# USB.net
KiCad netlist of a schematic drawn in Altium Designer
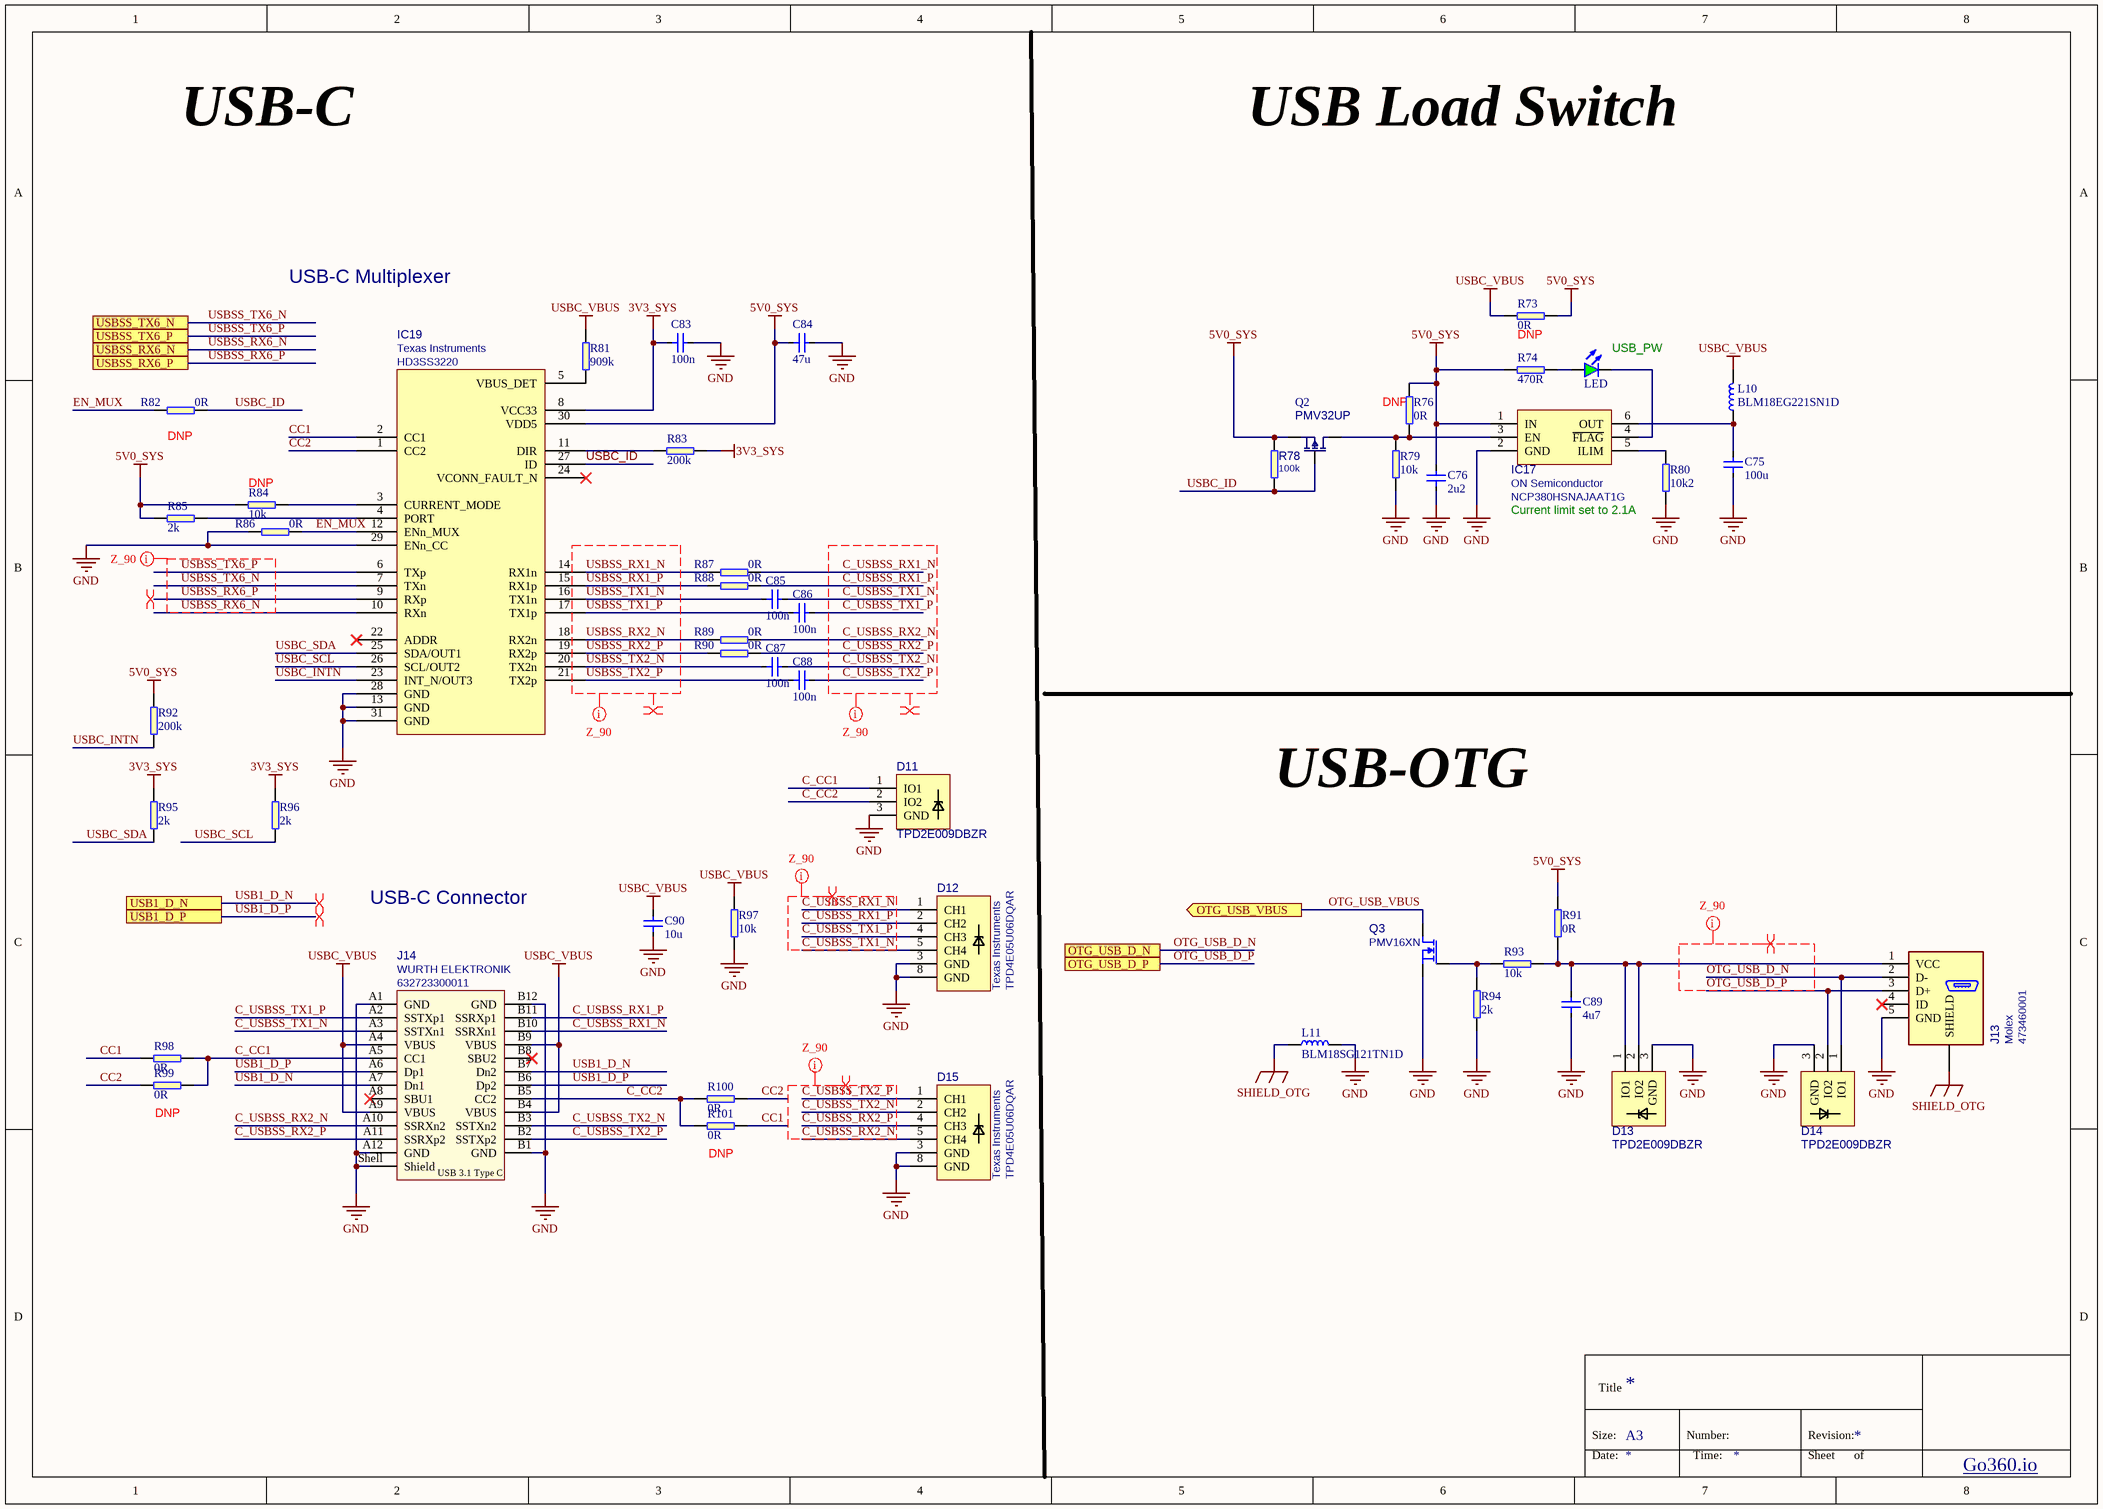
[diagram p0: USB.SchDoc]

(export (version "E")
  (design (tool "Eeschema 10.0.6"))
  (components
    (comp (ref "C75")
      (value "100u")
      (footprint "1206")
      (description "MLCC SMT Capacitor 100uF 1206")
      (fields (field (name "PARTNUMBER") "C_100u_1206") (field (name "MANUFACTURER") "Taiyo Yuden"))
      (libsource (lib "jetson-nano-baseboard") (part "C_100u_1206"))
    )
    (comp (ref "C76")
      (value "2u2")
      (footprint "C0402")
      (description "MLCC SMT Capacitor 2.2uF 0402")
      (fields (field (name "PARTNUMBER") "C_2u2_0402") (field (name "MANUFACTURER") "TDK"))
      (libsource (lib "jetson-nano-baseboard") (part "C_2u2_0402"))
    )
    (comp (ref "C83")
      (value "100n")
      (footprint "C0402")
      (description "MLCC SMT Capacitor 100n 0402")
      (fields (field (name "PARTNUMBER") "C_100n_0402") (field (name "MANUFACTURER") "TDK"))
      (libsource (lib "jetson-nano-baseboard") (part "C_100n_0402"))
    )
    (comp (ref "C84")
      (value "47u")
      (footprint "0805")
      (description "MLCC SMT Capacitor 47uF 0805")
      (fields (field (name "PARTNUMBER") "C_47u_0805") (field (name "MANUFACTURER") "KEMET"))
      (libsource (lib "jetson-nano-baseboard") (part "C_47u_0805"))
    )
    (comp (ref "C85")
      (value "100n")
      (footprint "C0402")
      (description "MLCC SMT Capacitor 100n 0402")
      (fields (field (name "PARTNUMBER") "C_100n_0402") (field (name "MANUFACTURER") "TDK"))
      (libsource (lib "jetson-nano-baseboard") (part "C_100n_0402"))
    )
    (comp (ref "C86")
      (value "100n")
      (footprint "C0402")
      (description "MLCC SMT Capacitor 100n 0402")
      (fields (field (name "PARTNUMBER") "C_100n_0402") (field (name "MANUFACTURER") "TDK"))
      (libsource (lib "jetson-nano-baseboard") (part "C_100n_0402"))
    )
    (comp (ref "C87")
      (value "100n")
      (footprint "C0402")
      (description "MLCC SMT Capacitor 100n 0402")
      (fields (field (name "PARTNUMBER") "C_100n_0402") (field (name "MANUFACTURER") "TDK"))
      (libsource (lib "jetson-nano-baseboard") (part "C_100n_0402"))
    )
    (comp (ref "C88")
      (value "100n")
      (footprint "C0402")
      (description "MLCC SMT Capacitor 100n 0402")
      (fields (field (name "PARTNUMBER") "C_100n_0402") (field (name "MANUFACTURER") "TDK"))
      (libsource (lib "jetson-nano-baseboard") (part "C_100n_0402"))
    )
    (comp (ref "C89")
      (value "4u7")
      (footprint "C0402")
      (description "MLCC SMT Capacitor 4.7uF 0402")
      (fields (field (name "PARTNUMBER") "C_4u7_0402") (field (name "MANUFACTURER") "MURATA"))
      (libsource (lib "jetson-nano-baseboard") (part "C_4u7_0402"))
    )
    (comp (ref "C90")
      (value "10u")
      (footprint "C0603")
      (description "MLCC SMT Capacitor 10uF 0603")
      (fields (field (name "PARTNUMBER") "C_10u_0603") (field (name "MANUFACTURER") "Walsin"))
      (libsource (lib "jetson-nano-baseboard") (part "C_10u_0603"))
    )
    (comp (ref "D11")
      (value "TPD2E009DBZR")
      (footprint "SOT-23")
      (description "DIODE, SCHOTTKY, 30V, 200MA, SOT-23")
      (fields (field (name "MANUFACTURER") "NXP"))
      (libsource (lib "") (part "TPD2E009DBZR_1"))
    )
    (comp (ref "D12")
      (value "TPD4E05U06")
      (footprint "TPD4E05U06_PASS")
      (description "ESD Suppressors 4-CH")
      (fields
        (field (name "PARTNUMBER") "TPD4E05U06_PASS")
        (field (name "MANUFACTURER") "Texas Instruments")
        (field (name "PARTSYMBOL") "TPD4E05U06DQAR")
      )
      (libsource (lib "jetson-nano-baseboard") (part "TPD4E05U06"))
    )
    (comp (ref "D13")
      (value "TPD2E009DBZR")
      (footprint "SOT-23s")
      (description "DIODE, SCHOTTKY, 30V, 200MA, SOT-23")
      (fields (field (name "MANUFACTURER") "NXP"))
      (libsource (lib "") (part "TPD2E009DBZR_2"))
    )
    (comp (ref "D14")
      (value "TPD2E009DBZR")
      (footprint "SOT-23s")
      (description "DIODE, SCHOTTKY, 30V, 200MA, SOT-23")
      (fields (field (name "MANUFACTURER") "NXP"))
      (libsource (lib "jetson-nano-baseboard") (part "TPD2E009DBZR"))
    )
    (comp (ref "D15")
      (value "TPD4E05U06")
      (footprint "TPD4E05U06_PASS")
      (description "ESD Suppressors 4-CH")
      (fields
        (field (name "PARTNUMBER") "TPD4E05U06_PASS")
        (field (name "MANUFACTURER") "Texas Instruments")
        (field (name "PARTSYMBOL") "TPD4E05U06DQAR")
      )
      (libsource (lib "jetson-nano-baseboard") (part "TPD4E05U06"))
    )
    (comp (ref "IC17")
      (value "NCP380HSNAJAAT1G")
      (footprint "TSOP-6")
      (description "POWER LOAD SWITCH, HIGH SIDE")
      (fields (field (name "MANUFACTURER") "ON Semiconductor"))
      (libsource (lib "jetson-nano-baseboard") (part "NCP380HSNAJAAT1G"))
    )
    (comp (ref "IC19")
      (value "HD3SS3220")
      (footprint "RNH0030A")
      (description "IC DRP PORT CTLR USB-C 30WQFN")
      (fields (field (name "MANUFACTURER") "Texas Instruments"))
      (libsource (lib "jetson-nano-baseboard") (part "HD3SS3220"))
    )
    (comp (ref "J13")
      (value "Molex 47346-0001")
      (footprint "CON-Molex-047346-0001")
      (description "USB - micro B Receptacle Connector 5 Position Surface Mount, Right Angle, Horizontal")
      (fields
        (field (name "PARTNUMBER") "CON-Molex-47346-0001")
        (field (name "MANUFACTURER") "Molex")
        (field (name "PARTSYMBOL") "473460001")
      )
      (libsource (lib "jetson-nano-baseboard") (part "Micro USB B"))
    )
    (comp (ref "J14")
      (value "632723300011")
      (footprint "WE_632723300011")
      (description "USB 3.1 Type C Receptacle Horizontal THR WR-COM")
      (fields (field (name "PARTNUMBER") "WE_632723300011") (field (name "MANUFACTURER") "WURTH ELEKTRONIK"))
      (libsource (lib "jetson-nano-baseboard") (part "WE_632723300011"))
    )
    (comp (ref "L10")
      (value "BLM18EG221SN1D")
      (footprint "BEADC1608X65N")
      (description "MURATA  BLM18EG221SN1D  FERRITE BEAD, 0.05OHM, 2A, 0603")
      (fields (field (name "MANUFACTURER") "MURATA"))
      (libsource (lib "jetson-nano-baseboard") (part "BLM18EG221SN1D"))
    )
    (comp (ref "L11")
      (value "BLM18SG121TN1D")
      (footprint "BEADC1608X65N")
      (description "FERRITE BEAD, 0.025OHM, 3A, 0603")
      (fields (field (name "MANUFACTURER") "MURATA"))
      (libsource (lib "jetson-nano-baseboard") (part "BLM18SG121TN1D"))
    )
    (comp (ref "LED")
      (value "SML-310MTT86")
      (footprint "LED0603")
      (description "LED Green 0603 case")
      (fields (field (name "MANUFACTURER") "ROHM Semicon") (field (name "PARTNUMBER") "LED_G"))
      (libsource (lib "jetson-nano-baseboard") (part "LED"))
    )
    (comp (ref "Q2")
      (value "PMV32UP")
      (footprint "SOT-23s")
      (description "P CH, 20V, 4A")
      (fields (field (name "MANUFACTURER") "NXP"))
      (libsource (lib "jetson-nano-baseboard") (part "PMOS"))
    )
    (comp (ref "Q3")
      (value "PMV16XN")
      (footprint "SOT-23s")
      (description "MOSFET, N CH")
      (fields (field (name "MANUFACTURER") "NXP"))
      (libsource (lib "jetson-nano-baseboard") (part "NMOS_PMV16XN"))
    )
    (comp (ref "R73")
      (value "0R")
      (footprint "R0402")
      (description "RES, 0R, 0402")
      (fields (field (name "PARTNUMBER") "R_0R_0402") (field (name "MANUFACTURER") "Panasonic"))
      (libsource (lib "") (part "R_0R_0402_1"))
    )
    (comp (ref "R74")
      (value "470R")
      (footprint "R0402")
      (description "RES, 470R, 0402")
      (fields (field (name "PARTNUMBER") "R_470R_0402") (field (name "MANUFACTURER") "VISHAY"))
      (libsource (lib "jetson-nano-baseboard") (part "R_470R_0402"))
    )
    (comp (ref "R76")
      (value "0R")
      (footprint "R0402")
      (description "RES, 0R, 0402")
      (fields (field (name "PARTNUMBER") "R_0R_0402") (field (name "MANUFACTURER") "Panasonic"))
      (libsource (lib "") (part "R_0R_0402_2"))
    )
    (comp (ref "R78")
      (value "100k")
      (footprint "R0402")
      (description "SMT Resistor 100k 0402")
      (fields (field (name "PARTNUMBER") "R_100k_0402") (field (name "TOLERANCE") "1%"))
      (libsource (lib "jetson-nano-baseboard") (part "R_100k_0402"))
    )
    (comp (ref "R79")
      (value "10k")
      (footprint "R0402")
      (description "RES, 10k, 0402")
      (fields (field (name "PARTNUMBER") "R_10k_0402") (field (name "MANUFACTURER") "MULTICOMP"))
      (libsource (lib "jetson-nano-baseboard") (part "R_10k_0402"))
    )
    (comp (ref "R80")
      (value "10k2")
      (footprint "R0402")
      (description "RES, 10k2, 0402, 0.1%")
      (fields (field (name "PARTNUMBER") "R_10k2_0402_0.1%") (field (name "TOLERANCE") "0.1%"))
      (libsource (lib "jetson-nano-baseboard") (part "R_10k2_0402"))
    )
    (comp (ref "R81")
      (value "909k")
      (footprint "R0402")
      (description "RES, 909k, 0402")
      (fields (field (name "PARTNUMBER") "R_909k_0402") (field (name "MANUFACTURER") "Panasonic"))
      (libsource (lib "jetson-nano-baseboard") (part "R_909k_0402"))
    )
    (comp (ref "R82")
      (value "0R")
      (footprint "R0402")
      (description "RES, 0R, 0402")
      (fields (field (name "PARTNUMBER") "R_0R_0402") (field (name "MANUFACTURER") "Panasonic"))
      (libsource (lib "") (part "R_0R_0402_1"))
    )
    (comp (ref "R83")
      (value "200k")
      (footprint "R0402")
      (description "RES, 200k, 0402")
      (fields (field (name "PARTNUMBER") "R_200k_0402") (field (name "MANUFACTURER") "YAGEO"))
      (libsource (lib "jetson-nano-baseboard") (part "R_200k_0402"))
    )
    (comp (ref "R84")
      (value "10k")
      (footprint "R0402")
      (description "RES, 10k, 0402")
      (fields (field (name "PARTNUMBER") "R_10k_0402") (field (name "MANUFACTURER") "MULTICOMP"))
      (libsource (lib "") (part "R_10k_0402_1"))
    )
    (comp (ref "R85")
      (value "2k")
      (footprint "R0402")
      (description "RES, 2k, 0402")
      (fields (field (name "PARTNUMBER") "R_2k_0402") (field (name "MANUFACTURER") "VISHAY"))
      (libsource (lib "") (part "R_2k_0402_1"))
    )
    (comp (ref "R86")
      (value "0R")
      (footprint "R0402")
      (description "RES, 0R, 0402")
      (fields (field (name "PARTNUMBER") "R_0R_0402") (field (name "MANUFACTURER") "Panasonic"))
      (libsource (lib "") (part "R_0R_0402_1"))
    )
    (comp (ref "R87")
      (value "0R")
      (footprint "R0402")
      (description "RES, 0R, 0402")
      (fields (field (name "PARTNUMBER") "R_0R_0402") (field (name "MANUFACTURER") "Panasonic"))
      (libsource (lib "") (part "R_0R_0402_1"))
    )
    (comp (ref "R88")
      (value "0R")
      (footprint "R0402")
      (description "RES, 0R, 0402")
      (fields (field (name "PARTNUMBER") "R_0R_0402") (field (name "MANUFACTURER") "Panasonic"))
      (libsource (lib "") (part "R_0R_0402_1"))
    )
    (comp (ref "R89")
      (value "0R")
      (footprint "R0402")
      (description "RES, 0R, 0402")
      (fields (field (name "PARTNUMBER") "R_0R_0402") (field (name "MANUFACTURER") "Panasonic"))
      (libsource (lib "") (part "R_0R_0402_1"))
    )
    (comp (ref "R90")
      (value "0R")
      (footprint "R0402")
      (description "RES, 0R, 0402")
      (fields (field (name "PARTNUMBER") "R_0R_0402") (field (name "MANUFACTURER") "Panasonic"))
      (libsource (lib "") (part "R_0R_0402_1"))
    )
    (comp (ref "R91")
      (value "0R")
      (footprint "R0402")
      (description "RES, 0R, 0402")
      (fields (field (name "PARTNUMBER") "R_0R_0402") (field (name "MANUFACTURER") "Panasonic"))
      (libsource (lib "") (part "R_0R_0402_2"))
    )
    (comp (ref "R92")
      (value "200k")
      (footprint "R0402")
      (description "RES, 200k, 0402")
      (fields (field (name "PARTNUMBER") "R_200k_0402") (field (name "MANUFACTURER") "YAGEO"))
      (libsource (lib "") (part "R_200k_0402_1"))
    )
    (comp (ref "R93")
      (value "10k")
      (footprint "R0402")
      (description "RES, 10k, 0402")
      (fields (field (name "PARTNUMBER") "R_10k_0402") (field (name "MANUFACTURER") "MULTICOMP"))
      (libsource (lib "") (part "R_10k_0402_1"))
    )
    (comp (ref "R94")
      (value "2k")
      (footprint "R0402")
      (description "RES, 2k, 0402")
      (fields (field (name "PARTNUMBER") "R_2k_0402") (field (name "MANUFACTURER") "VISHAY"))
      (libsource (lib "jetson-nano-baseboard") (part "R_2k_0402"))
    )
    (comp (ref "R95")
      (value "2k")
      (footprint "R0402")
      (description "RES, 2k, 0402")
      (fields (field (name "PARTNUMBER") "R_2k_0402") (field (name "MANUFACTURER") "VISHAY"))
      (libsource (lib "jetson-nano-baseboard") (part "R_2k_0402"))
    )
    (comp (ref "R96")
      (value "2k")
      (footprint "R0402")
      (description "RES, 2k, 0402")
      (fields (field (name "PARTNUMBER") "R_2k_0402") (field (name "MANUFACTURER") "VISHAY"))
      (libsource (lib "jetson-nano-baseboard") (part "R_2k_0402"))
    )
    (comp (ref "R97")
      (value "10k")
      (footprint "R0402")
      (description "RES, 10k, 0402")
      (fields (field (name "PARTNUMBER") "R_10k_0402") (field (name "MANUFACTURER") "MULTICOMP"))
      (libsource (lib "jetson-nano-baseboard") (part "R_10k_0402"))
    )
    (comp (ref "R98")
      (value "0R")
      (footprint "R0402")
      (description "RES, 0R, 0402")
      (fields (field (name "PARTNUMBER") "R_0R_0402") (field (name "MANUFACTURER") "Panasonic"))
      (libsource (lib "jetson-nano-baseboard") (part "R_0R_0402"))
    )
    (comp (ref "R99")
      (value "0R")
      (footprint "R0402")
      (description "RES, 0R, 0402")
      (fields (field (name "PARTNUMBER") "R_0R_0402") (field (name "MANUFACTURER") "Panasonic"))
      (libsource (lib "jetson-nano-baseboard") (part "R_0R_0402"))
    )
    (comp (ref "R100")
      (value "0R")
      (footprint "R0402")
      (description "RES, 0R, 0402")
      (fields (field (name "PARTNUMBER") "R_0R_0402") (field (name "MANUFACTURER") "Panasonic"))
      (libsource (lib "jetson-nano-baseboard") (part "R_0R_0402"))
    )
    (comp (ref "R101")
      (value "0R")
      (footprint "R0402")
      (description "RES, 0R, 0402")
      (fields (field (name "PARTNUMBER") "R_0R_0402") (field (name "MANUFACTURER") "Panasonic"))
      (libsource (lib "jetson-nano-baseboard") (part "R_0R_0402"))
    )
  )
  (nets
    (net (code "1") (name "/CC1") (class "Default")
      (node (ref "IC19") (pin "2") (pinfunction "CC1_2") (pintype "passive"))
      (node (ref "R101") (pin "2") (pintype "passive"))
      (node (ref "R98") (pin "1") (pintype "passive"))
    )
    (net (code "2") (name "/CC2") (class "Default")
      (node (ref "IC19") (pin "1") (pinfunction "CC2_1") (pintype "passive"))
      (node (ref "R100") (pin "2") (pintype "passive"))
      (node (ref "R99") (pin "1") (pintype "passive"))
    )
    (net (code "3") (name "/C_CC1") (class "Default")
      (node (ref "D11") (pin "1") (pinfunction "IO1_1") (pintype "passive"))
      (node (ref "J14") (pin "A5") (pinfunction "CC1_A5") (pintype "passive"))
      (node (ref "R98") (pin "2") (pintype "passive"))
      (node (ref "R99") (pin "2") (pintype "passive"))
    )
    (net (code "4") (name "/C_CC2") (class "Default")
      (node (ref "D11") (pin "2") (pinfunction "IO2_2") (pintype "passive"))
      (node (ref "J14") (pin "B5") (pinfunction "CC2_B5") (pintype "passive"))
      (node (ref "R100") (pin "1") (pintype "passive"))
      (node (ref "R101") (pin "1") (pintype "passive"))
    )
    (net (code "5") (name "/C_USBSS_RX1_N") (class "Default")
      (node (ref "D12") (pin "1") (pinfunction "CH1_1") (pintype "passive"))
      (node (ref "J14") (pin "B10") (pinfunction "SSRXn1_B10") (pintype "passive"))
      (node (ref "R87") (pin "1") (pintype "passive"))
    )
    (net (code "6") (name "/C_USBSS_RX1_P") (class "Default")
      (node (ref "D12") (pin "2") (pinfunction "CH2_2") (pintype "passive"))
      (node (ref "J14") (pin "B11") (pinfunction "SSRXp1_B11") (pintype "passive"))
      (node (ref "R88") (pin "1") (pintype "passive"))
    )
    (net (code "7") (name "/C_USBSS_RX2_N") (class "Default")
      (node (ref "D15") (pin "5") (pinfunction "CH4_5") (pintype "passive"))
      (node (ref "J14") (pin "A10") (pinfunction "SSRXn2_A10") (pintype "passive"))
      (node (ref "R89") (pin "1") (pintype "passive"))
    )
    (net (code "8") (name "/C_USBSS_RX2_P") (class "Default")
      (node (ref "D15") (pin "4") (pinfunction "CH3_4") (pintype "passive"))
      (node (ref "J14") (pin "A11") (pinfunction "SSRXp2_A11") (pintype "passive"))
      (node (ref "R90") (pin "1") (pintype "passive"))
    )
    (net (code "9") (name "/C_USBSS_TX1_N") (class "Default")
      (node (ref "C85") (pin "2") (pinfunction "2_2") (pintype "passive"))
      (node (ref "D12") (pin "5") (pinfunction "CH4_5") (pintype "passive"))
      (node (ref "J14") (pin "A3") (pinfunction "SSTXn1_A3") (pintype "passive"))
    )
    (net (code "10") (name "/C_USBSS_TX1_P") (class "Default")
      (node (ref "C86") (pin "2") (pinfunction "2_2") (pintype "passive"))
      (node (ref "D12") (pin "4") (pinfunction "CH3_4") (pintype "passive"))
      (node (ref "J14") (pin "A2") (pinfunction "SSTXp1_A2") (pintype "passive"))
    )
    (net (code "11") (name "/C_USBSS_TX2_N") (class "Default")
      (node (ref "C87") (pin "2") (pinfunction "2_2") (pintype "passive"))
      (node (ref "D15") (pin "2") (pinfunction "CH2_2") (pintype "passive"))
      (node (ref "J14") (pin "B3") (pinfunction "SSTXn2_B3") (pintype "passive"))
    )
    (net (code "12") (name "/C_USBSS_TX2_P") (class "Default")
      (node (ref "C88") (pin "2") (pinfunction "2_2") (pintype "passive"))
      (node (ref "D15") (pin "1") (pinfunction "CH1_1") (pintype "passive"))
      (node (ref "J14") (pin "B2") (pinfunction "SSTXp2_B2") (pintype "passive"))
    )
    (net (code "13") (name "/EN_MUX") (class "Default")
      (node (ref "IC19") (pin "12") (pinfunction "ENn_MUX_12") (pintype "passive"))
      (node (ref "R82") (pin "2") (pintype "passive"))
      (node (ref "R86") (pin "1") (pintype "passive"))
    )
    (net (code "14") (name "/OTG_USB_D_N") (class "Default")
      (node (ref "D14") (pin "1") (pinfunction "IO1_1") (pintype "passive"))
      (node (ref "J13") (pin "2") (pinfunction "D-_2") (pintype "passive"))
    )
    (net (code "15") (name "/OTG_USB_D_P") (class "Default")
      (node (ref "D14") (pin "2") (pinfunction "IO2_2") (pintype "passive"))
      (node (ref "J13") (pin "3") (pinfunction "D+_3") (pintype "passive"))
    )
    (net (code "16") (name "/OTG_USB_VBUS") (class "Default")
      (node (ref "Q3") (pin "3") (pinfunction "D_3") (pintype "passive"))
    )
    (net (code "17") (name "/USB1_D_N") (class "Default")
      (node (ref "J14") (pin "A7") (pinfunction "Dn1_A7") (pintype "passive"))
      (node (ref "J14") (pin "B7") (pinfunction "Dn2_B7") (pintype "passive"))
    )
    (net (code "18") (name "/USB1_D_P") (class "Default")
      (node (ref "J14") (pin "A6") (pinfunction "Dp1_A6") (pintype "passive"))
      (node (ref "J14") (pin "B6") (pinfunction "Dp2_B6") (pintype "passive"))
    )
    (net (code "19") (name "/USBC_ID") (class "Default")
      (node (ref "IC19") (pin "27") (pinfunction "ID_27") (pintype "passive"))
      (node (ref "Q2") (pin "1") (pinfunction "G_1") (pintype "passive"))
      (node (ref "R78") (pin "2") (pintype "passive"))
      (node (ref "R82") (pin "1") (pintype "passive"))
    )
    (net (code "20") (name "/USBC_INTN") (class "Default")
      (node (ref "IC19") (pin "23") (pinfunction "INT_N/OUT3_23") (pintype "passive"))
      (node (ref "R92") (pin "1") (pintype "passive"))
    )
    (net (code "21") (name "/USBC_SCL") (class "Default")
      (node (ref "IC19") (pin "26") (pinfunction "SCL/OUT2_26") (pintype "passive"))
      (node (ref "R96") (pin "1") (pintype "passive"))
    )
    (net (code "22") (name "/USBC_SDA") (class "Default")
      (node (ref "IC19") (pin "25") (pinfunction "SDA/OUT1_25") (pintype "passive"))
      (node (ref "R95") (pin "1") (pintype "passive"))
    )
    (net (code "23") (name "/USBSS_RX1_N") (class "Default")
      (node (ref "IC19") (pin "14") (pinfunction "RX1n_14") (pintype "passive"))
      (node (ref "R87") (pin "2") (pintype "passive"))
    )
    (net (code "24") (name "/USBSS_RX1_P") (class "Default")
      (node (ref "IC19") (pin "15") (pinfunction "RX1p_15") (pintype "passive"))
      (node (ref "R88") (pin "2") (pintype "passive"))
    )
    (net (code "25") (name "/USBSS_RX2_N") (class "Default")
      (node (ref "IC19") (pin "18") (pinfunction "RX2n_18") (pintype "passive"))
      (node (ref "R89") (pin "2") (pintype "passive"))
    )
    (net (code "26") (name "/USBSS_RX2_P") (class "Default")
      (node (ref "IC19") (pin "19") (pinfunction "RX2p_19") (pintype "passive"))
      (node (ref "R90") (pin "2") (pintype "passive"))
    )
    (net (code "27") (name "/USBSS_RX6_N") (class "Default")
      (node (ref "IC19") (pin "10") (pinfunction "RXn_10") (pintype "passive"))
    )
    (net (code "28") (name "/USBSS_RX6_P") (class "Default")
      (node (ref "IC19") (pin "9") (pinfunction "RXp_9") (pintype "passive"))
    )
    (net (code "29") (name "/USBSS_TX1_N") (class "Default")
      (node (ref "C85") (pin "1") (pinfunction "1_1") (pintype "passive"))
      (node (ref "IC19") (pin "16") (pinfunction "TX1n_16") (pintype "passive"))
    )
    (net (code "30") (name "/USBSS_TX1_P") (class "Default")
      (node (ref "C86") (pin "1") (pinfunction "1_1") (pintype "passive"))
      (node (ref "IC19") (pin "17") (pinfunction "TX1p_17") (pintype "passive"))
    )
    (net (code "31") (name "/USBSS_TX2_N") (class "Default")
      (node (ref "C87") (pin "1") (pinfunction "1_1") (pintype "passive"))
      (node (ref "IC19") (pin "20") (pinfunction "TX2n_20") (pintype "passive"))
    )
    (net (code "32") (name "/USBSS_TX2_P") (class "Default")
      (node (ref "C88") (pin "1") (pinfunction "1_1") (pintype "passive"))
      (node (ref "IC19") (pin "21") (pinfunction "TX2p_21") (pintype "passive"))
    )
    (net (code "33") (name "/USBSS_TX6_N") (class "Default")
      (node (ref "IC19") (pin "7") (pinfunction "TXn_7") (pintype "passive"))
    )
    (net (code "34") (name "/USBSS_TX6_P") (class "Default")
      (node (ref "IC19") (pin "6") (pinfunction "TXp_6") (pintype "passive"))
    )
    (net (code "35") (name "3V3_SYS") (class "Default")
      (node (ref "C83") (pin "1") (pinfunction "1_1") (pintype "passive"))
      (node (ref "IC19") (pin "8") (pinfunction "VCC33_8") (pintype "passive"))
      (node (ref "R83") (pin "2") (pintype "passive"))
      (node (ref "R95") (pin "2") (pintype "passive"))
      (node (ref "R96") (pin "2") (pintype "passive"))
    )
    (net (code "36") (name "5V0_SYS") (class "Default")
      (node (ref "C76") (pin "2") (pinfunction "2_2") (pintype "passive"))
      (node (ref "C84") (pin "1") (pinfunction "1_1") (pintype "passive"))
      (node (ref "IC17") (pin "1") (pinfunction "IN_1") (pintype "passive"))
      (node (ref "IC19") (pin "30") (pinfunction "VDD5_30") (pintype "passive"))
      (node (ref "Q2") (pin "2") (pinfunction "S_2") (pintype "passive"))
      (node (ref "R73") (pin "1") (pintype "passive"))
      (node (ref "R74") (pin "1") (pintype "passive"))
      (node (ref "R76") (pin "2") (pintype "passive"))
      (node (ref "R78") (pin "1") (pintype "passive"))
      (node (ref "R84") (pin "1") (pintype "passive"))
      (node (ref "R85") (pin "1") (pintype "passive"))
      (node (ref "R91") (pin "2") (pintype "passive"))
      (node (ref "R92") (pin "2") (pintype "passive"))
    )
    (net (code "37") (name "GND") (class "Default")
      (node (ref "C75") (pin "1") (pinfunction "1_1") (pintype "passive"))
      (node (ref "C76") (pin "1") (pinfunction "1_1") (pintype "passive"))
      (node (ref "C83") (pin "2") (pinfunction "2_2") (pintype "passive"))
      (node (ref "C84") (pin "2") (pinfunction "2_2") (pintype "passive"))
      (node (ref "C89") (pin "1") (pinfunction "1_1") (pintype "passive"))
      (node (ref "C90") (pin "1") (pinfunction "1_1") (pintype "passive"))
      (node (ref "D11") (pin "3") (pinfunction "GND_3") (pintype "passive"))
      (node (ref "D12") (pin "3") (pinfunction "GND_3") (pintype "passive"))
      (node (ref "D12") (pin "8") (pinfunction "GND_8") (pintype "passive"))
      (node (ref "D13") (pin "3") (pinfunction "GND_3") (pintype "passive"))
      (node (ref "D14") (pin "3") (pinfunction "GND_3") (pintype "passive"))
      (node (ref "D15") (pin "3") (pinfunction "GND_3") (pintype "passive"))
      (node (ref "D15") (pin "8") (pinfunction "GND_8") (pintype "passive"))
      (node (ref "IC17") (pin "2") (pinfunction "GND_2") (pintype "passive"))
      (node (ref "IC19") (pin "13") (pinfunction "GND_13") (pintype "passive"))
      (node (ref "IC19") (pin "28") (pinfunction "GND_28") (pintype "passive"))
      (node (ref "IC19") (pin "29") (pinfunction "ENn_CC_29") (pintype "passive"))
      (node (ref "IC19") (pin "31") (pinfunction "GND_31") (pintype "passive"))
      (node (ref "J13") (pin "5") (pinfunction "GND_5") (pintype "power_in"))
      (node (ref "J14") (pin "A1") (pinfunction "GND_A1") (pintype "passive"))
      (node (ref "J14") (pin "A12") (pinfunction "GND_A12") (pintype "passive"))
      (node (ref "J14") (pin "B1") (pinfunction "GND_B1") (pintype "passive"))
      (node (ref "J14") (pin "B12") (pinfunction "GND_B12") (pintype "passive"))
      (node (ref "J14") (pin "Shell") (pinfunction "Shield_Shell") (pintype "passive"))
      (node (ref "L11") (pin "2") (pintype "passive"))
      (node (ref "Q3") (pin "2") (pinfunction "S_2") (pintype "passive"))
      (node (ref "R79") (pin "1") (pintype "passive"))
      (node (ref "R80") (pin "1") (pintype "passive"))
      (node (ref "R86") (pin "2") (pintype "passive"))
      (node (ref "R94") (pin "1") (pintype "passive"))
      (node (ref "R97") (pin "1") (pintype "passive"))
    )
    (net (code "38") (name "Net-(D13-IO1)") (class "Default")
      (node (ref "C89") (pin "2") (pinfunction "2_2") (pintype "passive"))
      (node (ref "D13") (pin "1") (pinfunction "IO1_1") (pintype "passive"))
      (node (ref "D13") (pin "2") (pinfunction "IO2_2") (pintype "passive"))
      (node (ref "J13") (pin "1") (pinfunction "VCC_1") (pintype "power_in"))
      (node (ref "R91") (pin "1") (pintype "passive"))
      (node (ref "R93") (pin "2") (pintype "passive"))
    )
    (net (code "39") (name "Net-(IC17-EN)") (class "Default")
      (node (ref "IC17") (pin "3") (pinfunction "EN_3") (pintype "passive"))
      (node (ref "Q2") (pin "3") (pinfunction "D_3") (pintype "passive"))
      (node (ref "R76") (pin "1") (pintype "passive"))
      (node (ref "R79") (pin "2") (pintype "passive"))
    )
    (net (code "40") (name "Net-(IC17-ILIM)") (class "Default")
      (node (ref "IC17") (pin "5") (pinfunction "ILIM_5") (pintype "passive"))
      (node (ref "R80") (pin "2") (pintype "passive"))
    )
    (net (code "41") (name "Net-(IC17-OUT)") (class "Default")
      (node (ref "C75") (pin "2") (pinfunction "2_2") (pintype "passive"))
      (node (ref "IC17") (pin "6") (pinfunction "OUT_6") (pintype "passive"))
      (node (ref "L10") (pin "1") (pintype "passive"))
    )
    (net (code "42") (name "Net-(IC17-~{FLAG})") (class "Default")
      (node (ref "IC17") (pin "4") (pinfunction "~{FLAG}_4") (pintype "passive"))
      (node (ref "LED") (pin "K") (pinfunction "K_K") (pintype "passive"))
    )
    (net (code "43") (name "Net-(IC19-CURRENT_MODE)") (class "Default")
      (node (ref "IC19") (pin "3") (pinfunction "CURRENT_MODE_3") (pintype "passive"))
      (node (ref "R84") (pin "2") (pintype "passive"))
    )
    (net (code "44") (name "Net-(IC19-DIR)") (class "Default")
      (node (ref "IC19") (pin "11") (pinfunction "DIR_11") (pintype "passive"))
      (node (ref "R83") (pin "1") (pintype "passive"))
    )
    (net (code "45") (name "Net-(IC19-PORT)") (class "Default")
      (node (ref "IC19") (pin "4") (pinfunction "PORT_4") (pintype "passive"))
      (node (ref "R85") (pin "2") (pintype "passive"))
    )
    (net (code "46") (name "Net-(IC19-VBUS_DET)") (class "Default")
      (node (ref "IC19") (pin "5") (pinfunction "VBUS_DET_5") (pintype "passive"))
      (node (ref "R81") (pin "1") (pintype "passive"))
    )
    (net (code "47") (name "Net-(LED-PadA)") (class "Default")
      (node (ref "LED") (pin "A") (pinfunction "A_A") (pintype "passive"))
      (node (ref "R74") (pin "2") (pintype "passive"))
    )
    (net (code "48") (name "Net-(Q3-G)") (class "Default")
      (node (ref "Q3") (pin "1") (pinfunction "G_1") (pintype "passive"))
      (node (ref "R93") (pin "1") (pintype "passive"))
      (node (ref "R94") (pin "2") (pintype "passive"))
    )
    (net (code "49") (name "SHIELD_OTG") (class "Default")
      (node (ref "J13") (pin "S") (pinfunction "SHIELD_S") (pintype "passive"))
      (node (ref "L11") (pin "1") (pintype "passive"))
    )
    (net (code "50") (name "USBC_VBUS") (class "Default")
      (node (ref "C90") (pin "2") (pinfunction "2_2") (pintype "passive"))
      (node (ref "J14") (pin "A4") (pinfunction "VBUS_A4") (pintype "passive"))
      (node (ref "J14") (pin "A9") (pinfunction "VBUS_A9") (pintype "passive"))
      (node (ref "J14") (pin "B4") (pinfunction "VBUS_B4") (pintype "passive"))
      (node (ref "J14") (pin "B9") (pinfunction "VBUS_B9") (pintype "passive"))
      (node (ref "L10") (pin "2") (pintype "passive"))
      (node (ref "R73") (pin "2") (pintype "passive"))
      (node (ref "R81") (pin "2") (pintype "passive"))
      (node (ref "R97") (pin "2") (pintype "passive"))
    )
    (net (code "51") (name "unconnected-(IC19-ADDR-Pad22)") (class "Default")
      (node (ref "IC19") (pin "22") (pinfunction "ADDR_22") (pintype "passive+no_connect"))
    )
    (net (code "52") (name "unconnected-(IC19-VCONN_FAULT_N-Pad24)") (class "Default")
      (node (ref "IC19") (pin "24") (pinfunction "VCONN_FAULT_N_24") (pintype "passive+no_connect"))
    )
    (net (code "53") (name "unconnected-(J13-ID-Pad4)") (class "Default")
      (node (ref "J13") (pin "4") (pinfunction "ID_4") (pintype "passive+no_connect"))
    )
    (net (code "54") (name "unconnected-(J14-SBU1-PadA8)") (class "Default")
      (node (ref "J14") (pin "A8") (pinfunction "SBU1_A8") (pintype "passive+no_connect"))
    )
    (net (code "55") (name "unconnected-(J14-SBU2-PadB8)") (class "Default")
      (node (ref "J14") (pin "B8") (pinfunction "SBU2_B8") (pintype "passive+no_connect"))
    )
  )
)
